# PA0960_IR_Dot_Projector_IR_Flood_LED.net
KiCad netlist of a schematic drawn in Altium Designer
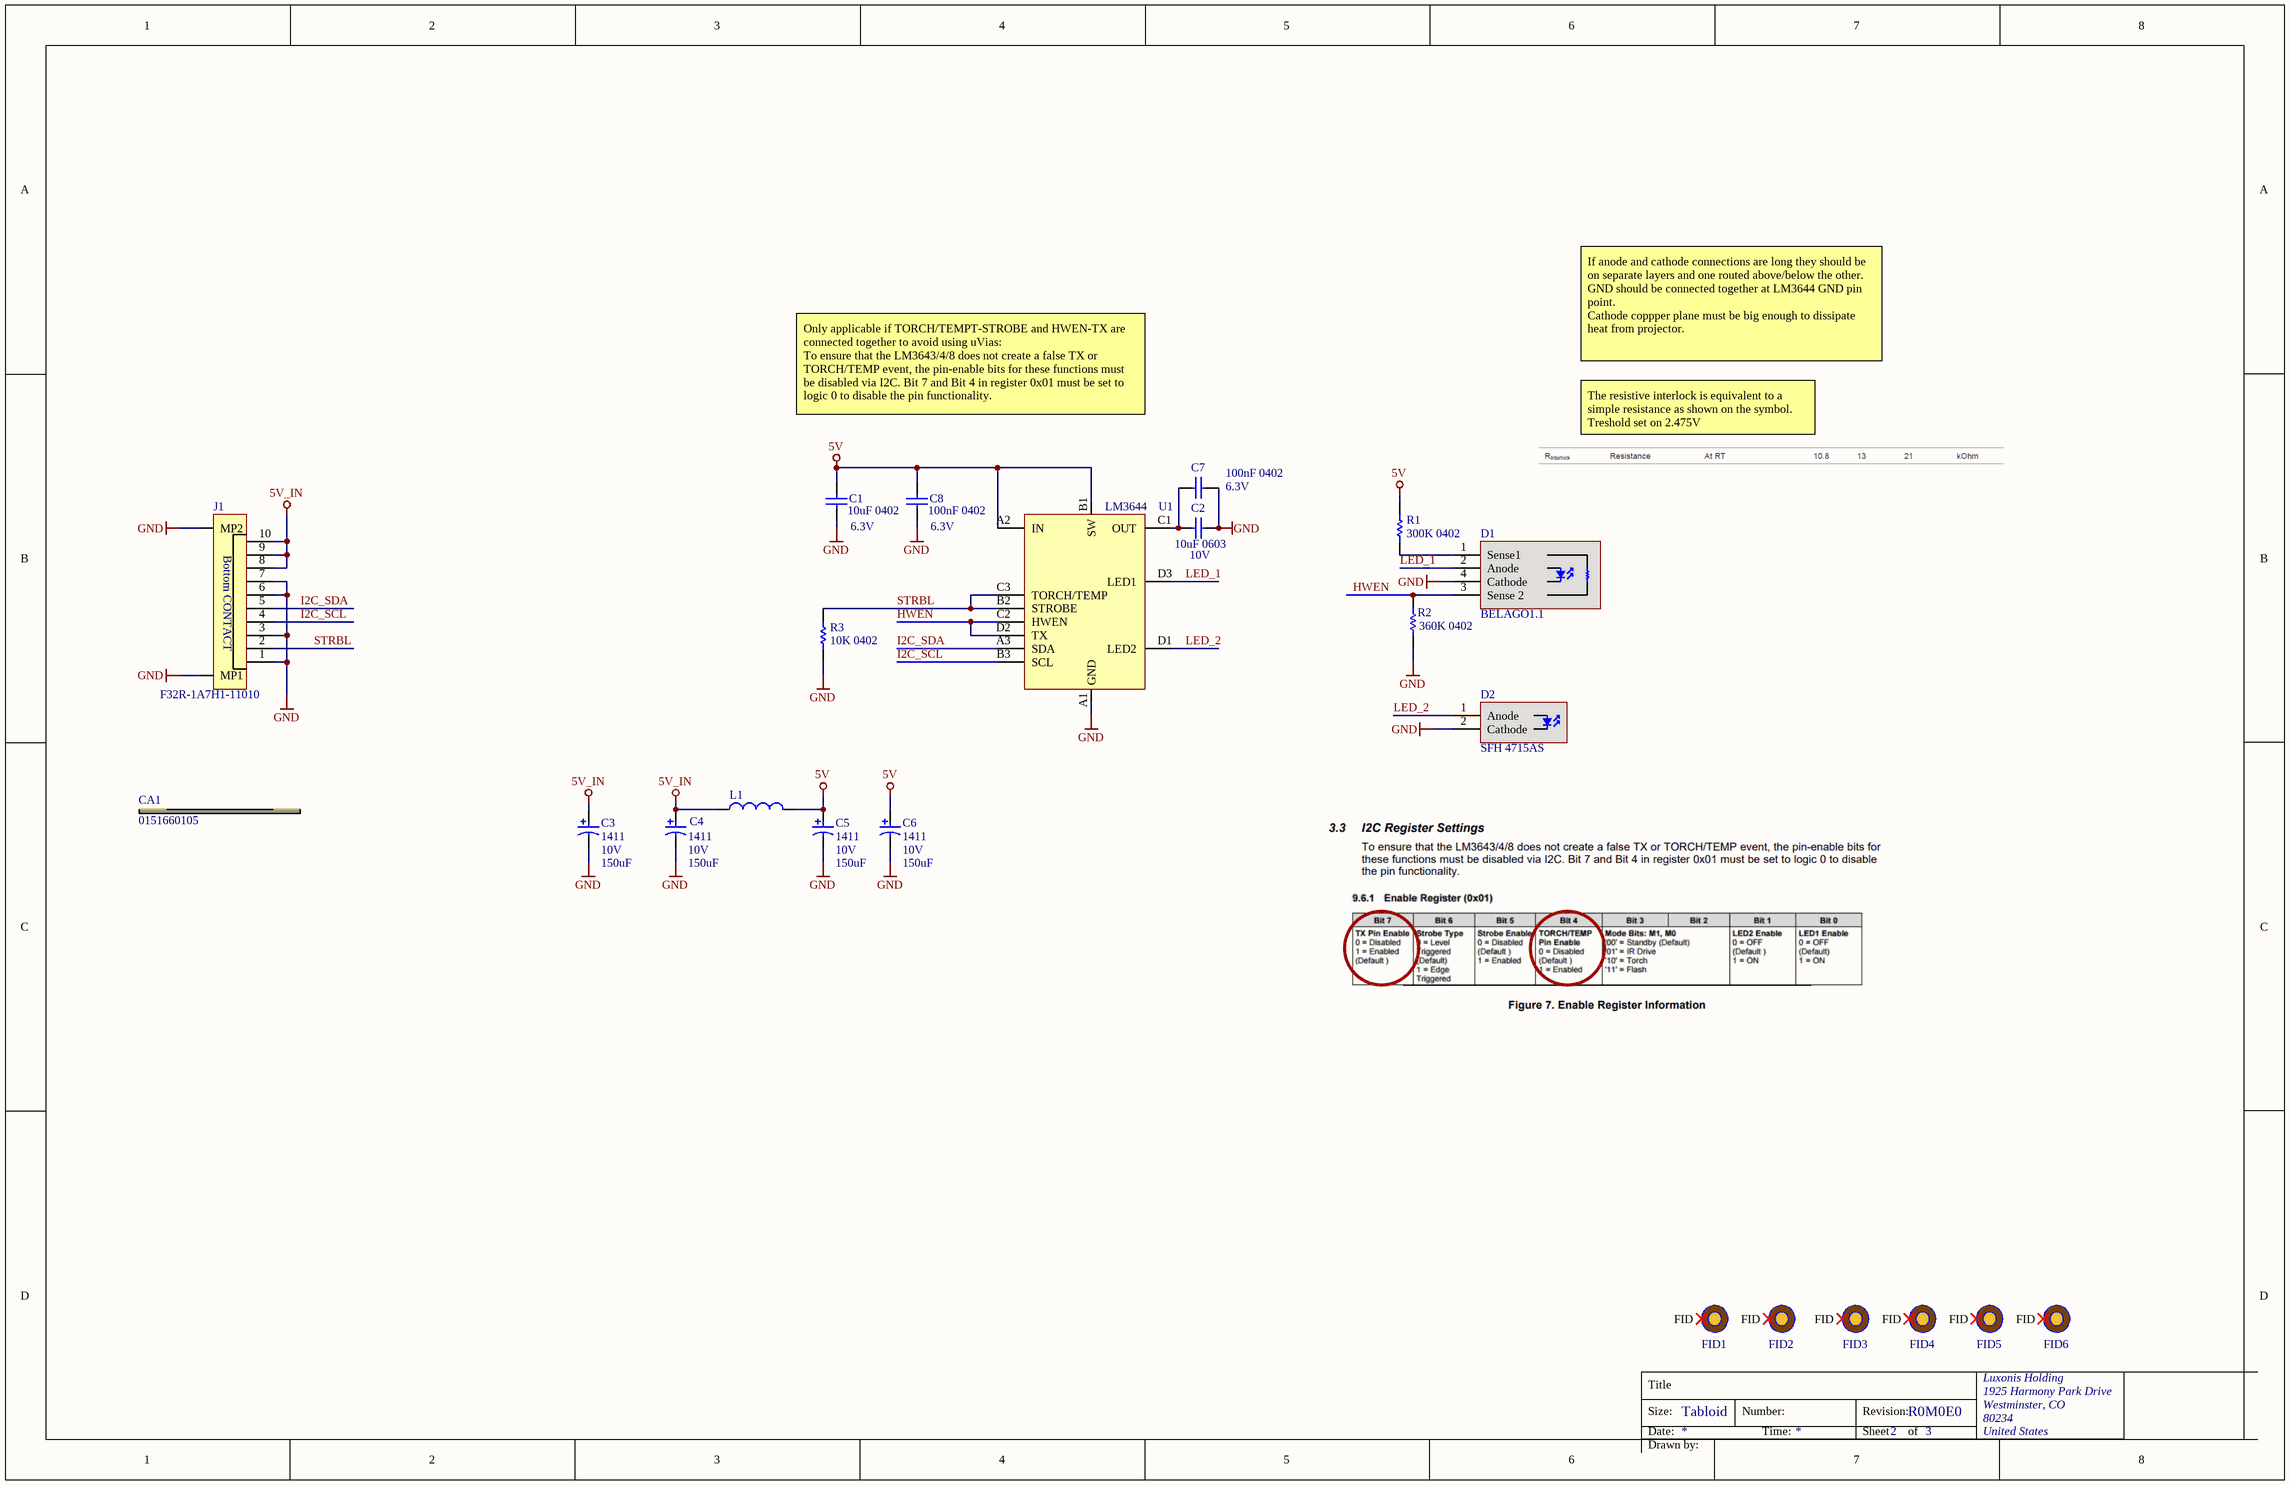
[diagram p0: PA0960_IR_Dot_Projector_IR_Flood_LED.SchDoc]

(export (version "E")
  (design (tool "Eeschema 10.0.6"))
  (components
    (comp (ref "C1")
      (value "10uF 0402")
      (footprint "CAPC0402(1005)70_N")
      (description "CAP CER 10UF 6.3V X5R 0402 20%")
      (fields (field (name "VOLTAGE RATING") "6.3V") (field (name "TOLERANCE") "20%"))
      (libsource (lib "Luxonis LLC") (part "LLL153C70G474ME17E"))
    )
    (comp (ref "C2")
      (value "10uF 0603")
      (footprint "CAPC0603(1608)100_N")
      (description "CAP CER 10UF 10V X5R 0603 20%")
      (fields (field (name "VOLTAGE RATING") "10V") (field (name "TOLERANCE") "20%"))
      (libsource (lib "Luxonis LLC") (part "LLL153C70G474ME17E"))
    )
    (comp (ref "C3")
      (value "150uF 1206 10V tantal")
      (footprint "RESTL1210(3225)_L")
      (fields
        (field (name "SIZE CODE") "1411")
        (field (name "RATED DC VOLTAGE (URDC)") "10V")
        (field (name "CAPACITANCE") "150uF")
      )
      (libsource (lib "Luxonis LLC") (part "TLJB157M010R0500"))
    )
    (comp (ref "C4")
      (value "150uF 1206 10V tantal")
      (footprint "RESTL1210(3225)_L")
      (fields
        (field (name "SIZE CODE") "1411")
        (field (name "RATED DC VOLTAGE (URDC)") "10V")
        (field (name "CAPACITANCE") "150uF")
      )
      (libsource (lib "Luxonis LLC") (part "TLJB157M010R0500"))
    )
    (comp (ref "C5")
      (value "150uF 1206 10V tantal")
      (footprint "RESTL1210(3225)_L")
      (fields
        (field (name "SIZE CODE") "1411")
        (field (name "RATED DC VOLTAGE (URDC)") "10V")
        (field (name "CAPACITANCE") "150uF")
      )
      (libsource (lib "Luxonis LLC") (part "TLJB157M010R0500"))
    )
    (comp (ref "C6")
      (value "150uF 1206 10V tantal")
      (footprint "RESTL1210(3225)_L")
      (fields
        (field (name "SIZE CODE") "1411")
        (field (name "RATED DC VOLTAGE (URDC)") "10V")
        (field (name "CAPACITANCE") "150uF")
      )
      (libsource (lib "Luxonis LLC") (part "TLJB157M010R0500"))
    )
    (comp (ref "C7")
      (value "100nF 0402")
      (footprint "CAPC0402(1005)70_N")
      (description "CAP CER 10UF 6.3V X5R 0402 20%")
      (fields (field (name "VOLTAGE RATING") "6.3V") (field (name "TOLERANCE") "20%"))
      (libsource (lib "Luxonis LLC") (part "LLL153C70G474ME17E"))
    )
    (comp (ref "C8")
      (value "100nF 0402")
      (footprint "CAPC0402(1005)70_N")
      (description "CAP CER 10UF 6.3V X5R 0402 20%")
      (fields (field (name "VOLTAGE RATING") "6.3V") (field (name "TOLERANCE") "20%"))
      (libsource (lib "Luxonis LLC") (part "LLL153C70G474ME17E"))
    )
    (comp (ref "CA1")
      (value "0151660105")
      (description "CABLE FFC 10POS 0.50MM 6\"")
      (libsource (lib "Luxonis LLC") (part "CMP-00006-1"))
    )
    (comp (ref "D1")
      (value "BELAGO1.1")
      (footprint "Belago1.1")
      (description "Dot-Pattern Infrared Illuminator for 3D Stereoscopic\r\nImaging AQAA-20")
      (libsource (lib "Luxonis LLC") (part "BELAGO1.1"))
    )
    (comp (ref "D2")
      (value "SFH 4715AS")
      (footprint "SFH 4715AS")
      (description "OSLON Black Series (850 nm) - 80°")
      (libsource (lib "Luxonis LLC") (part "SFH 4715AS"))
    )
    (comp (ref "FID1")
      (value "FIDUCIAL_ROUND_1MM")
      (footprint "FIDUCIAL_ROUND_1MM")
      (description "Fiducial with various available footprints")
      (libsource (lib "Luxonis LLC") (part "FIDUCIAL"))
    )
    (comp (ref "FID2")
      (value "FIDUCIAL_ROUND_1MM")
      (footprint "FIDUCIAL_ROUND_1MM")
      (description "Fiducial with various available footprints")
      (libsource (lib "Luxonis LLC") (part "FIDUCIAL"))
    )
    (comp (ref "FID3")
      (value "FIDUCIAL_ROUND_1MM")
      (footprint "FIDUCIAL_ROUND_1MM")
      (description "Fiducial with various available footprints")
      (libsource (lib "Luxonis LLC") (part "FIDUCIAL"))
    )
    (comp (ref "FID4")
      (value "FIDUCIAL_ROUND_1MM")
      (footprint "FIDUCIAL_ROUND_1MM")
      (description "Fiducial with various available footprints")
      (libsource (lib "Luxonis LLC") (part "FIDUCIAL"))
    )
    (comp (ref "FID5")
      (value "FIDUCIAL_ROUND_1MM")
      (footprint "FIDUCIAL_ROUND_1MM")
      (description "Fiducial with various available footprints")
      (libsource (lib "Luxonis LLC") (part "FIDUCIAL"))
    )
    (comp (ref "FID6")
      (value "FIDUCIAL_ROUND_1MM")
      (footprint "FIDUCIAL_ROUND_1MM")
      (description "Fiducial with various available footprints")
      (libsource (lib "Luxonis LLC") (part "FIDUCIAL"))
    )
    (comp (ref "J1")
      (value "F32R-1A7H1-11010")
      (footprint "F32R-1A7H1-11010")
      (description "FPC/FFC Connector Socket 10 Position 0.5mm Bottom Contact Solder Right Angle Surface Mount T/R")
      (libsource (lib "Luxonis LLC") (part "F32R-1A7H1-11010"))
    )
    (comp (ref "L1")
      (value "742792011")
      (footprint "SMD-0805")
      (description "Ferrite Chip, 1 Function(s), 3A, 2 Pin(s)")
      (libsource (lib "Luxonis LLC") (part "IND-2"))
    )
    (comp (ref "R1")
      (value "300K 0402")
      (footprint "RESC0402(1005)_L")
      (fields (field (name "TOLERANCE") "1%"))
      (libsource (lib "Luxonis LLC") (part "RC0402FR-0722RL_1"))
    )
    (comp (ref "R2")
      (value "360K 0402")
      (footprint "RESC0402(1005)_N")
      (fields (field (name "TOLERANCE") "1%"))
      (libsource (lib "Luxonis LLC") (part "CR0402-FX-2492GLF"))
    )
    (comp (ref "R3")
      (value "10K 0402")
      (footprint "RESC0402(1005)_L")
      (fields (field (name "TOLERANCE") "1%"))
      (libsource (lib "Luxonis LLC") (part "RC0402FR-0722RL_1"))
    )
    (comp (ref "U1")
      (value "LM3644")
      (footprint "LM3644YFFR")
      (description "LED Driver, 2-Segment, PBGA12")
      (libsource (lib "Luxonis LLC") (part "LM3644"))
    )
  )
  (nets
    (net (code "1") (name "/HWEN") (class "Default")
      (node (ref "D1") (pin "3") (pinfunction "Sense_2_3") (pintype "passive"))
      (node (ref "R2") (pin "2") (pinfunction "2_2") (pintype "passive"))
      (node (ref "U1") (pin "C2") (pinfunction "HWEN_C2") (pintype "passive"))
      (node (ref "U1") (pin "D2") (pinfunction "TX_D2") (pintype "passive"))
    )
    (net (code "2") (name "/I2C_SCL") (class "Default")
      (node (ref "J1") (pin "4") (pinfunction "4_4") (pintype "passive"))
      (node (ref "U1") (pin "B3") (pinfunction "SCL_B3") (pintype "passive"))
    )
    (net (code "3") (name "/I2C_SDA") (class "Default")
      (node (ref "J1") (pin "5") (pinfunction "5_5") (pintype "passive"))
      (node (ref "U1") (pin "A3") (pinfunction "SDA_A3") (pintype "passive"))
    )
    (net (code "4") (name "/LED_1") (class "Default")
      (node (ref "D1") (pin "2") (pinfunction "Anode_2") (pintype "passive"))
      (node (ref "U1") (pin "D3") (pinfunction "LED1_D3") (pintype "passive"))
    )
    (net (code "5") (name "/LED_2") (class "Default")
      (node (ref "D2") (pin "1") (pinfunction "Anode_1") (pintype "passive"))
      (node (ref "U1") (pin "D1") (pinfunction "LED2_D1") (pintype "passive"))
    )
    (net (code "6") (name "/STRBL") (class "Default")
      (node (ref "J1") (pin "2") (pinfunction "2_2") (pintype "passive"))
      (node (ref "R3") (pin "2") (pinfunction "2_2") (pintype "passive"))
      (node (ref "U1") (pin "B2") (pinfunction "STROBE_B2") (pintype "passive"))
      (node (ref "U1") (pin "C3") (pinfunction "TORCH/TEMP_C3") (pintype "passive"))
    )
    (net (code "7") (name "5V") (class "Default")
      (node (ref "C1") (pin "2") (pinfunction "2_2") (pintype "passive"))
      (node (ref "C5") (pin "1") (pinfunction "1_1") (pintype "passive"))
      (node (ref "C6") (pin "1") (pinfunction "1_1") (pintype "passive"))
      (node (ref "C8") (pin "2") (pinfunction "2_2") (pintype "passive"))
      (node (ref "L1") (pin "2") (pinfunction "2_2") (pintype "passive"))
      (node (ref "R1") (pin "2") (pinfunction "2_2") (pintype "passive"))
      (node (ref "U1") (pin "A2") (pinfunction "IN_A2") (pintype "passive"))
      (node (ref "U1") (pin "B1") (pinfunction "SW_B1") (pintype "passive"))
    )
    (net (code "8") (name "5V_IN") (class "Default")
      (node (ref "C3") (pin "1") (pinfunction "1_1") (pintype "passive"))
      (node (ref "C4") (pin "1") (pinfunction "1_1") (pintype "passive"))
      (node (ref "J1") (pin "10") (pinfunction "10_10") (pintype "passive"))
      (node (ref "J1") (pin "8") (pinfunction "8_8") (pintype "passive"))
      (node (ref "J1") (pin "9") (pinfunction "9_9") (pintype "passive"))
      (node (ref "L1") (pin "1") (pinfunction "1_1") (pintype "passive"))
    )
    (net (code "9") (name "GND") (class "Default")
      (node (ref "C1") (pin "1") (pinfunction "1_1") (pintype "passive"))
      (node (ref "C2") (pin "2") (pinfunction "2_2") (pintype "passive"))
      (node (ref "C3") (pin "2") (pinfunction "2_2") (pintype "passive"))
      (node (ref "C4") (pin "2") (pinfunction "2_2") (pintype "passive"))
      (node (ref "C5") (pin "2") (pinfunction "2_2") (pintype "passive"))
      (node (ref "C6") (pin "2") (pinfunction "2_2") (pintype "passive"))
      (node (ref "C7") (pin "1") (pinfunction "1_1") (pintype "passive"))
      (node (ref "C8") (pin "1") (pinfunction "1_1") (pintype "passive"))
      (node (ref "D1") (pin "4") (pinfunction "Cathode_4") (pintype "passive"))
      (node (ref "D2") (pin "2") (pinfunction "Cathode_2") (pintype "passive"))
      (node (ref "J1") (pin "1") (pinfunction "1_1") (pintype "passive"))
      (node (ref "J1") (pin "3") (pinfunction "3_3") (pintype "passive"))
      (node (ref "J1") (pin "6") (pinfunction "6_6") (pintype "passive"))
      (node (ref "J1") (pin "7") (pinfunction "7_7") (pintype "passive"))
      (node (ref "J1") (pin "MP1") (pinfunction "MP1_MP1") (pintype "passive"))
      (node (ref "J1") (pin "MP2") (pinfunction "MP2_MP2") (pintype "passive"))
      (node (ref "R2") (pin "1") (pinfunction "1_1") (pintype "passive"))
      (node (ref "R3") (pin "1") (pinfunction "1_1") (pintype "passive"))
      (node (ref "U1") (pin "A1") (pinfunction "GND_A1") (pintype "passive"))
    )
    (net (code "10") (name "Net-(D1-Sense1)") (class "Default")
      (node (ref "D1") (pin "1") (pinfunction "Sense1_1") (pintype "passive"))
      (node (ref "R1") (pin "1") (pinfunction "1_1") (pintype "passive"))
    )
    (net (code "11") (name "Net-(U1-OUT)") (class "Default")
      (node (ref "C2") (pin "1") (pinfunction "1_1") (pintype "passive"))
      (node (ref "C7") (pin "2") (pinfunction "2_2") (pintype "passive"))
      (node (ref "U1") (pin "C1") (pinfunction "OUT_C1") (pintype "passive"))
    )
    (net (code "12") (name "unconnected-(FID1-PadFID)") (class "Default")
      (node (ref "FID1") (pin "FID") (pinfunction "FID_FID") (pintype "input+no_connect"))
    )
    (net (code "13") (name "unconnected-(FID2-PadFID)") (class "Default")
      (node (ref "FID2") (pin "FID") (pinfunction "FID_FID") (pintype "input+no_connect"))
    )
    (net (code "14") (name "unconnected-(FID3-PadFID)") (class "Default")
      (node (ref "FID3") (pin "FID") (pinfunction "FID_FID") (pintype "input+no_connect"))
    )
    (net (code "15") (name "unconnected-(FID4-PadFID)") (class "Default")
      (node (ref "FID4") (pin "FID") (pinfunction "FID_FID") (pintype "input+no_connect"))
    )
    (net (code "16") (name "unconnected-(FID5-PadFID)") (class "Default")
      (node (ref "FID5") (pin "FID") (pinfunction "FID_FID") (pintype "input+no_connect"))
    )
    (net (code "17") (name "unconnected-(FID6-PadFID)") (class "Default")
      (node (ref "FID6") (pin "FID") (pinfunction "FID_FID") (pintype "input+no_connect"))
    )
  )
)
